# Sensors.net
KiCad netlist of a schematic drawn in Altium Designer
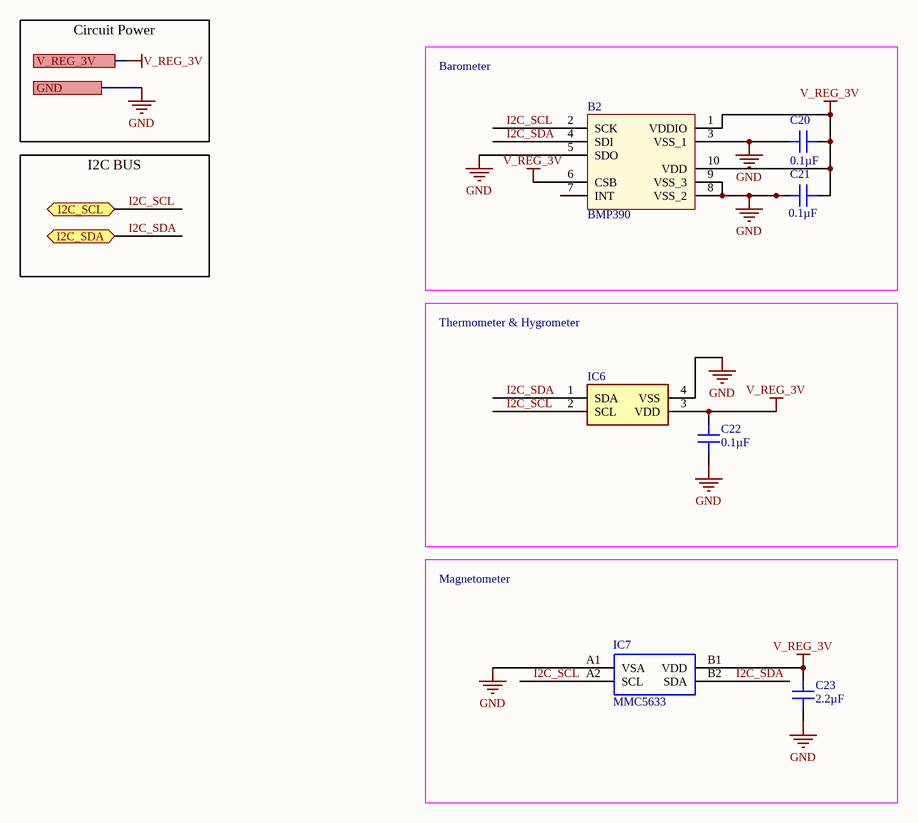
[diagram p0: Sensors.SchDoc]

(export (version "E")
  (design (tool "Eeschema 10.0.6"))
  (components
    (comp (ref "B2")
      (value "BMP390")
      (footprint "BMP390")
      (description "PRESSURE")
      (fields (field (name "MOUSER PART NUMBER") "262-BMP390") (field (name "MANUFACTURER") "BOSCH"))
      (libsource (lib "MVVVMAltiumDatabase") (part "BOSCH BMP390"))
    )
    (comp (ref "C20")
      (value "0.1µF")
      (footprint "CAP 0603_1608 RF")
      (description "CAP CER 0.1UF 16V X7R 0603")
      (fields (field (name "MANUFACTURER") "KEMET") (field (name "VOLTAGE") "16V"))
      (libsource (lib "MVVVMAltiumDatabase") (part "Capacitor"))
    )
    (comp (ref "C21")
      (value "0.1µF")
      (footprint "CAP 0603_1608 RF")
      (description "CAP CER 0.1UF 16V X7R 0603")
      (fields (field (name "MANUFACTURER") "KEMET") (field (name "VOLTAGE") "16V"))
      (libsource (lib "MVVVMAltiumDatabase") (part "Capacitor"))
    )
    (comp (ref "C22")
      (value "0.1µF")
      (footprint "CAP 0402_1005")
      (description "CAP CER 0.1UF 16V X7R 0402")
      (fields (field (name "MANUFACTURER") "KEMET") (field (name "VOLTAGE") "16V"))
      (libsource (lib "MVVVMAltiumDatabase") (part "Capacitor"))
    )
    (comp (ref "C23")
      (value "2.2µF")
      (footprint "CAP 0402_1005 RF")
      (description "CAP CER 2.2UF 10V X7S 0402")
      (fields (field (name "MANUFACTURER") "Murata Electronics") (field (name "VOLTAGE") "10V"))
      (libsource (lib "MVVVMAltiumDatabase") (part "Capacitor"))
    )
    (comp (ref "IC6")
      (value "-40°C ~ 125°C Temp Sense")
      (footprint "SENSIRION SHT45")
      (description "SENSOR HUMID/TEMP HIGH ACCURACY")
      (fields (field (name "MANUFACTURER") "Sensirion AG"))
      (libsource (lib "MVVVMAltiumDatabase") (part "SENSIRION SHT45"))
    )
    (comp (ref "IC7")
      (value "MMC5633")
      (footprint "MEMSIC MMC5633")
      (description "30 GAUSS, MONOLITHIC, HIGH PERFO")
      (fields (field (name "MANUFACTURER") "MEMSIC"))
      (libsource (lib "MVVVMAltiumDatabase") (part "MEMSIC MMC5633"))
    )
  )
  (nets
    (net (code "1") (name "/I2C_SCL") (class "Default")
      (node (ref "B2") (pin "2") (pinfunction "SCK_2") (pintype "passive"))
      (node (ref "IC6") (pin "2") (pinfunction "SCL_2") (pintype "passive"))
      (node (ref "IC7") (pin "A2") (pinfunction "SCL_A2") (pintype "passive"))
    )
    (net (code "2") (name "/I2C_SDA") (class "Default")
      (node (ref "B2") (pin "4") (pinfunction "SDI_4") (pintype "passive"))
      (node (ref "IC6") (pin "1") (pinfunction "SDA_1") (pintype "passive"))
      (node (ref "IC7") (pin "B2") (pinfunction "SDA_B2") (pintype "passive"))
    )
    (net (code "3") (name "GND") (class "Default")
      (node (ref "B2") (pin "3") (pinfunction "VSS_1_3") (pintype "passive"))
      (node (ref "B2") (pin "5") (pinfunction "SDO_5") (pintype "passive"))
      (node (ref "B2") (pin "8") (pinfunction "VSS_2_8") (pintype "passive"))
      (node (ref "B2") (pin "9") (pinfunction "VSS_3_9") (pintype "passive"))
      (node (ref "C20") (pin "1") (pinfunction "1_1") (pintype "passive"))
      (node (ref "C21") (pin "1") (pinfunction "1_1") (pintype "passive"))
      (node (ref "C22") (pin "1") (pinfunction "1_1") (pintype "passive"))
      (node (ref "C23") (pin "1") (pinfunction "1_1") (pintype "passive"))
      (node (ref "IC6") (pin "4") (pinfunction "VSS_4") (pintype "passive"))
      (node (ref "IC7") (pin "A1") (pinfunction "VSA_A1") (pintype "passive"))
    )
    (net (code "4") (name "V_REG_3V") (class "Default")
      (node (ref "B2") (pin "1") (pinfunction "VDDIO_1") (pintype "passive"))
      (node (ref "B2") (pin "10") (pinfunction "VDD_10") (pintype "passive"))
      (node (ref "B2") (pin "6") (pinfunction "CSB_6") (pintype "passive"))
      (node (ref "C20") (pin "2") (pinfunction "2_2") (pintype "passive"))
      (node (ref "C21") (pin "2") (pinfunction "2_2") (pintype "passive"))
      (node (ref "C22") (pin "2") (pinfunction "2_2") (pintype "passive"))
      (node (ref "C23") (pin "2") (pinfunction "2_2") (pintype "passive"))
      (node (ref "IC6") (pin "3") (pinfunction "VDD_3") (pintype "passive"))
      (node (ref "IC7") (pin "B1") (pinfunction "VDD_B1") (pintype "passive"))
    )
    (net (code "5") (name "unconnected-(B2-INT-Pad7)") (class "Default")
      (node (ref "B2") (pin "7") (pinfunction "INT_7") (pintype "passive"))
    )
  )
)
